# HPR_wo_comm.net
KiCad netlist of a schematic drawn in EAGLE
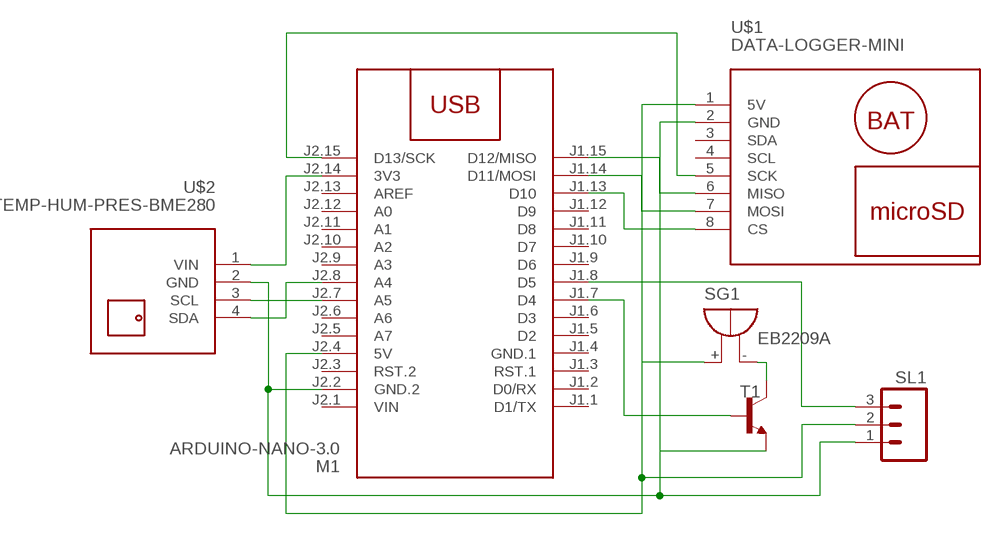
[diagram p0: schematic, sheet 1]

(export (version "E")
  (design (tool "Eeschema 10.0.6"))
  (components
    (comp (ref "M1")
      (value "ARDUINO-NANO-3.0")
      (footprint "eagle-import:ARDUINO-NANO-3.0")
      (libsource (lib "eagle-import") (part "ARDUINO-NANO-3.0"))
    )
    (comp (ref "SG1")
      (value "EB2209A")
      (footprint "eagle-import:EB2209A")
      (libsource (lib "eagle-import") (part "EB2209A"))
    )
    (comp (ref "SL1")
      (value "M03")
      (footprint "eagle-import:03P")
      (libsource (lib "eagle-import") (part "M03"))
    )
    (comp (ref "T1")
      (value "2N3700-NPN-TO18-EBC")
      (footprint "eagle-import:TO18")
      (libsource (lib "eagle-import") (part "-NPN-TO18-EBC2N3700"))
    )
    (comp (ref "U$1")
      (value "DATA-LOGGER-MINI")
      (footprint "eagle-import:DATA-LOGGER-MINI")
      (libsource (lib "eagle-import") (part "DATA-LOGGER-MINI"))
    )
    (comp (ref "U$2")
      (value "TEMP-HUM-PRES-BME280")
      (footprint "eagle-import:TEMP-HUM-PRES-BME280")
      (libsource (lib "eagle-import") (part "TEMP-HUM-PRES-BME280"))
    )
  )
  (nets
    (net (code "1") (name "/GND.1") (class "Default")
      (node (ref "M1") (pin "J1.4") (pinfunction "GND.1_J1.4") (pintype "power_in"))
    )
    (net (code "2") (name "/VIN") (class "Default")
      (node (ref "M1") (pin "J2.1") (pinfunction "VIN_J2.1") (pintype "power_in"))
    )
    (net (code "3") (name "Net-(M1-3V3)") (class "Default")
      (node (ref "M1") (pin "J2.14") (pinfunction "3V3_J2.14") (pintype "power_in"))
      (node (ref "U$2") (pin "1") (pinfunction "VIN_1") (pintype "power_in"))
    )
    (net (code "4") (name "Net-(M1-5V)") (class "Default")
      (node (ref "M1") (pin "J2.4") (pinfunction "5V_J2.4") (pintype "power_in"))
      (node (ref "SG1") (pin "+") (pinfunction "+_+") (pintype "passive"))
      (node (ref "SL1") (pin "2") (pinfunction "2_2") (pintype "passive"))
      (node (ref "U$1") (pin "1") (pinfunction "5V_1") (pintype "power_in"))
    )
    (net (code "5") (name "Net-(M1-A4)") (class "Default")
      (node (ref "M1") (pin "J2.8") (pinfunction "A4_J2.8") (pintype "bidirectional"))
      (node (ref "U$2") (pin "4") (pinfunction "SDA_4") (pintype "bidirectional"))
    )
    (net (code "6") (name "Net-(M1-A5)") (class "Default")
      (node (ref "M1") (pin "J2.7") (pinfunction "A5_J2.7") (pintype "bidirectional"))
      (node (ref "U$2") (pin "3") (pinfunction "SCL_3") (pintype "bidirectional"))
    )
    (net (code "7") (name "Net-(M1-D4)") (class "Default")
      (node (ref "M1") (pin "J1.7") (pinfunction "D4_J1.7") (pintype "bidirectional"))
      (node (ref "T1") (pin "2") (pinfunction "B_2") (pintype "passive"))
    )
    (net (code "8") (name "Net-(M1-D5)") (class "Default")
      (node (ref "M1") (pin "J1.8") (pinfunction "D5_J1.8") (pintype "bidirectional"))
      (node (ref "SL1") (pin "3") (pinfunction "3_3") (pintype "passive"))
    )
    (net (code "9") (name "Net-(M1-D10)") (class "Default")
      (node (ref "M1") (pin "J1.13") (pinfunction "D10_J1.13") (pintype "bidirectional"))
      (node (ref "U$1") (pin "8") (pinfunction "CS_8") (pintype "power_in"))
    )
    (net (code "10") (name "Net-(M1-D11{slash}MOSI)") (class "Default")
      (node (ref "M1") (pin "J1.14") (pinfunction "D11/MOSI_J1.14") (pintype "bidirectional"))
      (node (ref "U$1") (pin "7") (pinfunction "MOSI_7") (pintype "bidirectional"))
    )
    (net (code "11") (name "Net-(M1-D12{slash}MISO)") (class "Default")
      (node (ref "M1") (pin "J1.15") (pinfunction "D12/MISO_J1.15") (pintype "bidirectional"))
      (node (ref "U$1") (pin "6") (pinfunction "MISO_6") (pintype "bidirectional"))
    )
    (net (code "12") (name "Net-(M1-D13{slash}SCK)") (class "Default")
      (node (ref "M1") (pin "J2.15") (pinfunction "D13/SCK_J2.15") (pintype "bidirectional"))
      (node (ref "U$1") (pin "5") (pinfunction "SCK_5") (pintype "bidirectional"))
    )
    (net (code "13") (name "Net-(M1-GND.2)") (class "Default")
      (node (ref "M1") (pin "J2.2") (pinfunction "GND.2_J2.2") (pintype "power_in"))
      (node (ref "SL1") (pin "1") (pinfunction "1_1") (pintype "passive"))
      (node (ref "T1") (pin "1") (pinfunction "E_1") (pintype "passive"))
      (node (ref "U$1") (pin "2") (pinfunction "GND_2") (pintype "power_in"))
      (node (ref "U$2") (pin "2") (pinfunction "GND_2") (pintype "power_in"))
    )
    (net (code "14") (name "Net-(T1-C)") (class "Default")
      (node (ref "SG1") (pin "-") (pinfunction "-_-") (pintype "passive"))
      (node (ref "T1") (pin "3") (pinfunction "C_3") (pintype "passive"))
    )
    (net (code "15") (name "unconnected-(M1-A0-PadJ2.12)") (class "Default")
      (node (ref "M1") (pin "J2.12") (pinfunction "A0_J2.12") (pintype "bidirectional"))
    )
    (net (code "16") (name "unconnected-(M1-A1-PadJ2.11)") (class "Default")
      (node (ref "M1") (pin "J2.11") (pinfunction "A1_J2.11") (pintype "bidirectional"))
    )
    (net (code "17") (name "unconnected-(M1-A2-PadJ2.10)") (class "Default")
      (node (ref "M1") (pin "J2.10") (pinfunction "A2_J2.10") (pintype "bidirectional"))
    )
    (net (code "18") (name "unconnected-(M1-A3-PadJ2.9)") (class "Default")
      (node (ref "M1") (pin "J2.9") (pinfunction "A3_J2.9") (pintype "bidirectional"))
    )
    (net (code "19") (name "unconnected-(M1-A6-PadJ2.6)") (class "Default")
      (node (ref "M1") (pin "J2.6") (pinfunction "A6_J2.6") (pintype "bidirectional"))
    )
    (net (code "20") (name "unconnected-(M1-A7-PadJ2.5)") (class "Default")
      (node (ref "M1") (pin "J2.5") (pinfunction "A7_J2.5") (pintype "bidirectional"))
    )
    (net (code "21") (name "unconnected-(M1-AREF-PadJ2.13)") (class "Default")
      (node (ref "M1") (pin "J2.13") (pinfunction "AREF_J2.13") (pintype "bidirectional"))
    )
    (net (code "22") (name "unconnected-(M1-D0{slash}RX-PadJ1.2)") (class "Default")
      (node (ref "M1") (pin "J1.2") (pinfunction "D0/RX_J1.2") (pintype "bidirectional"))
    )
    (net (code "23") (name "unconnected-(M1-D1{slash}TX-PadJ1.1)") (class "Default")
      (node (ref "M1") (pin "J1.1") (pinfunction "D1/TX_J1.1") (pintype "bidirectional"))
    )
    (net (code "24") (name "unconnected-(M1-D2-PadJ1.5)") (class "Default")
      (node (ref "M1") (pin "J1.5") (pinfunction "D2_J1.5") (pintype "bidirectional"))
    )
    (net (code "25") (name "unconnected-(M1-D3-PadJ1.6)") (class "Default")
      (node (ref "M1") (pin "J1.6") (pinfunction "D3_J1.6") (pintype "bidirectional"))
    )
    (net (code "26") (name "unconnected-(M1-D6-PadJ1.9)") (class "Default")
      (node (ref "M1") (pin "J1.9") (pinfunction "D6_J1.9") (pintype "bidirectional"))
    )
    (net (code "27") (name "unconnected-(M1-D7-PadJ1.10)") (class "Default")
      (node (ref "M1") (pin "J1.10") (pinfunction "D7_J1.10") (pintype "bidirectional"))
    )
    (net (code "28") (name "unconnected-(M1-D8-PadJ1.11)") (class "Default")
      (node (ref "M1") (pin "J1.11") (pinfunction "D8_J1.11") (pintype "bidirectional"))
    )
    (net (code "29") (name "unconnected-(M1-D9-PadJ1.12)") (class "Default")
      (node (ref "M1") (pin "J1.12") (pinfunction "D9_J1.12") (pintype "bidirectional"))
    )
    (net (code "30") (name "unconnected-(M1-RST.1-PadJ1.3)") (class "Default")
      (node (ref "M1") (pin "J1.3") (pinfunction "RST.1_J1.3") (pintype "bidirectional"))
    )
    (net (code "31") (name "unconnected-(M1-RST.2-PadJ2.3)") (class "Default")
      (node (ref "M1") (pin "J2.3") (pinfunction "RST.2_J2.3") (pintype "bidirectional"))
    )
    (net (code "32") (name "unconnected-(U$1-SCL-Pad4)") (class "Default")
      (node (ref "U$1") (pin "4") (pinfunction "SCL_4") (pintype "bidirectional"))
    )
    (net (code "33") (name "unconnected-(U$1-SDA-Pad3)") (class "Default")
      (node (ref "U$1") (pin "3") (pinfunction "SDA_3") (pintype "bidirectional"))
    )
  )
)
